# synthesizer-RF-Si4123.net
KiCad netlist of a schematic drawn in EAGLE
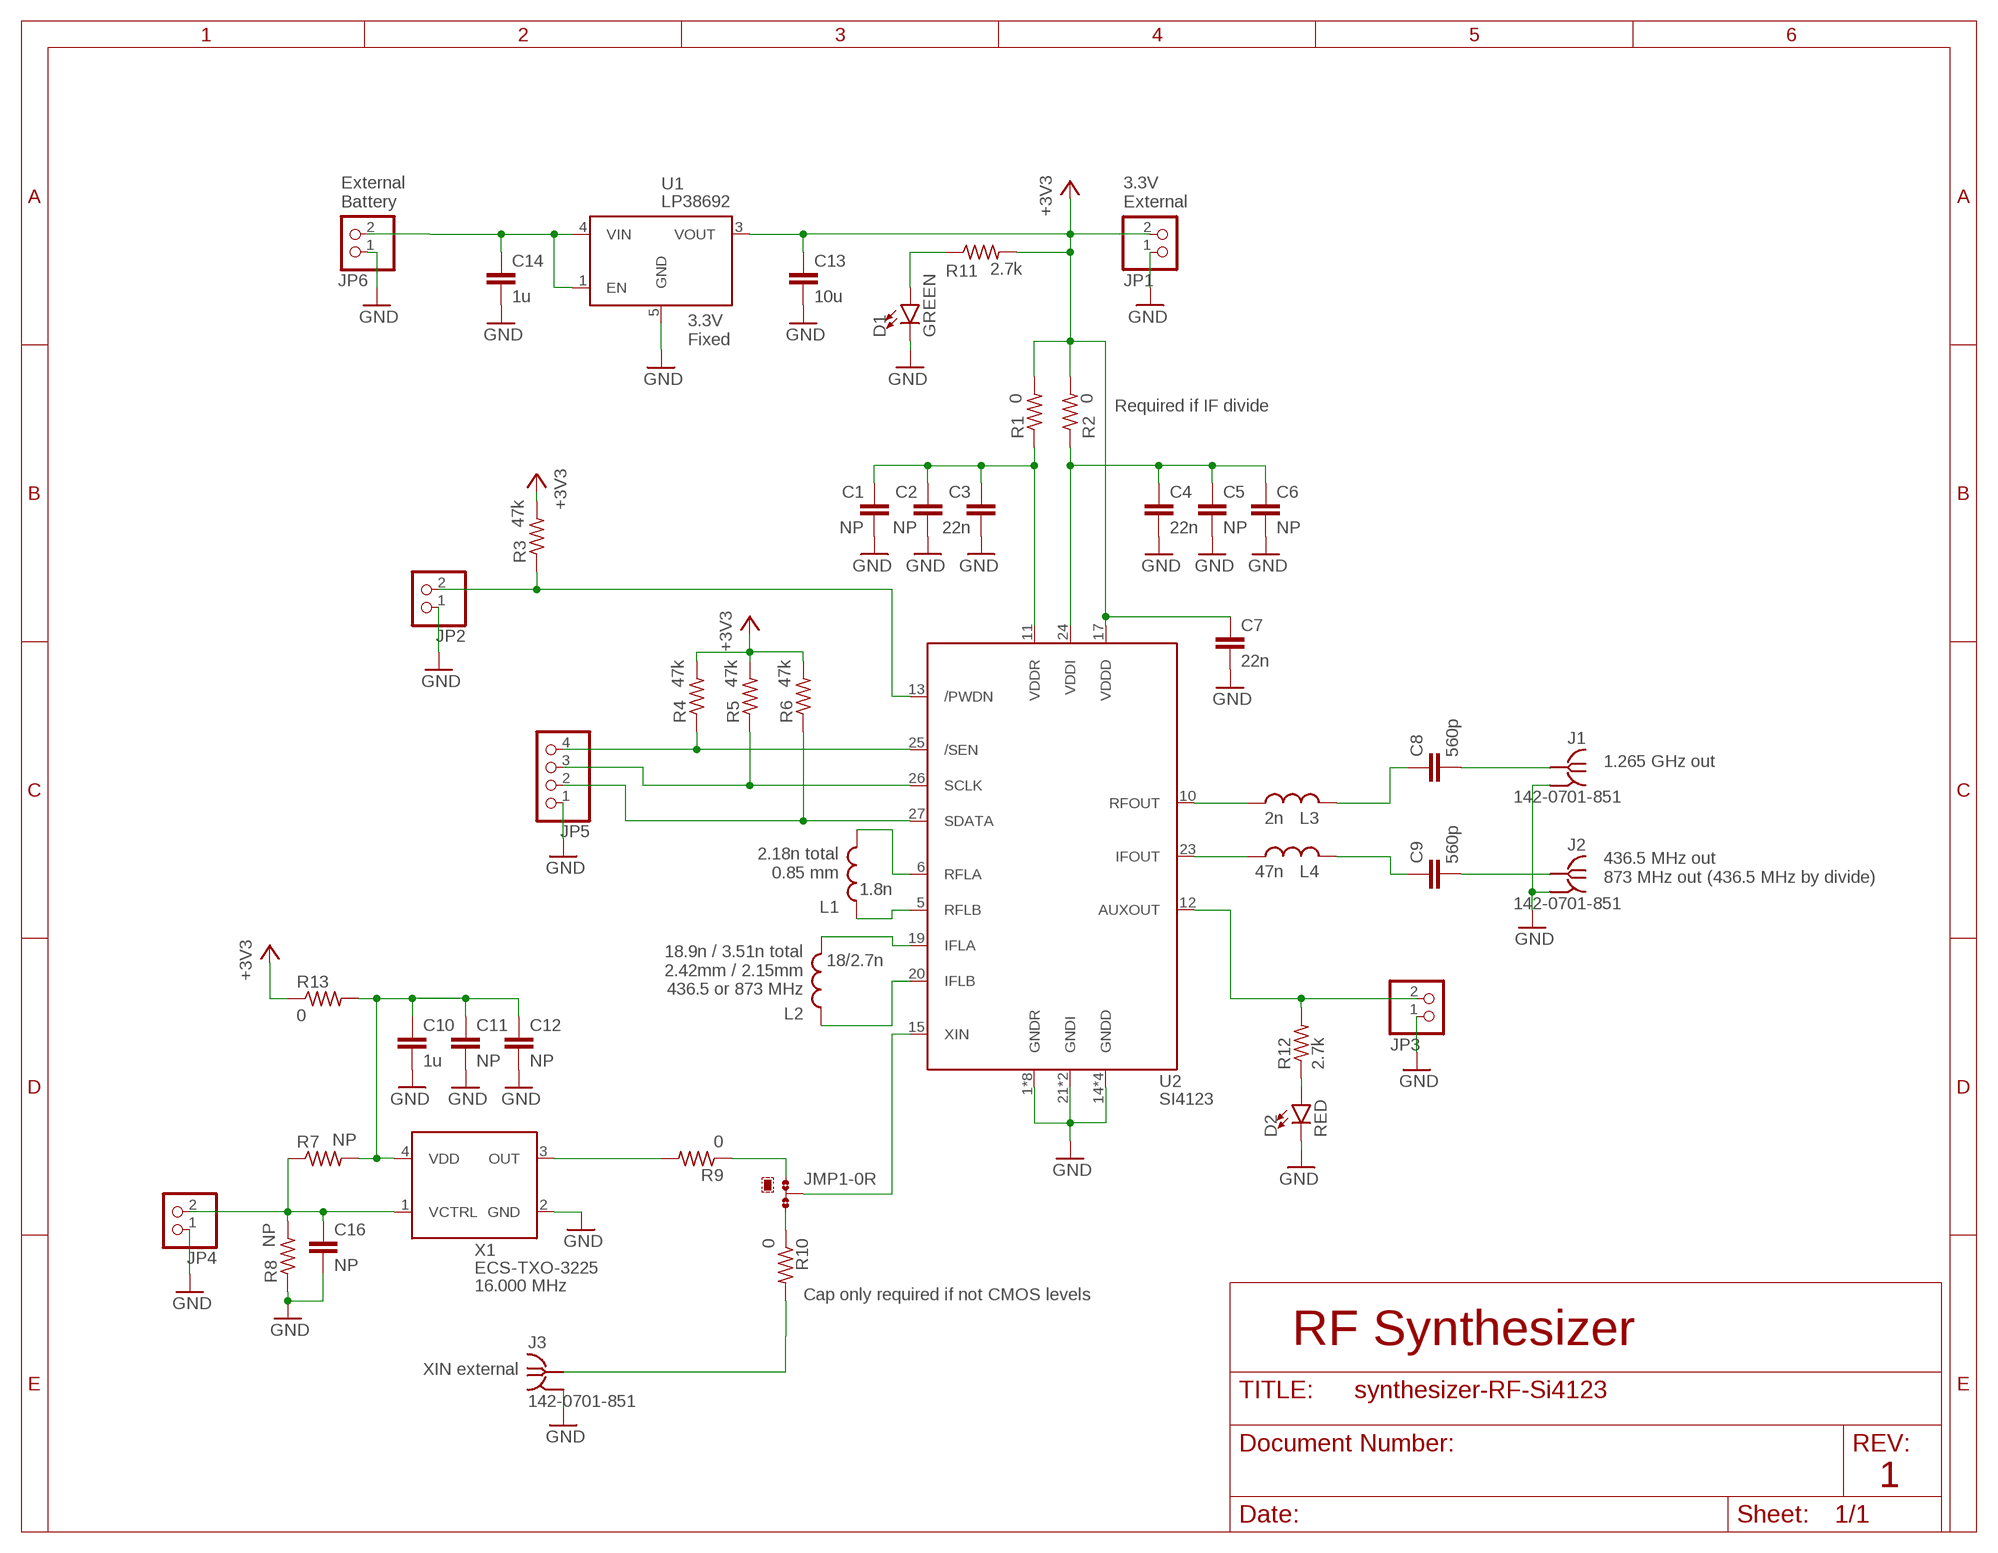
[diagram p0: schematic, sheet 1]

(export (version "E")
  (design (tool "Eeschema 10.0.6"))
  (components
    (comp (ref "C1")
      (value "NP")
      (footprint "eagle-import:.0603-B-NOSILK")
      (libsource (lib "eagle-import") (part "C-EU0603-B-NOSILK"))
    )
    (comp (ref "C2")
      (value "NP")
      (footprint "eagle-import:.0603-B-NOSILK")
      (libsource (lib "eagle-import") (part "C-EU0603-B-NOSILK"))
    )
    (comp (ref "C3")
      (value "22n")
      (footprint "eagle-import:.0603-B-NOSILK")
      (libsource (lib "eagle-import") (part "C-EU0603-B-NOSILK"))
    )
    (comp (ref "C4")
      (value "22n")
      (footprint "eagle-import:.0603-B-NOSILK")
      (libsource (lib "eagle-import") (part "C-EU0603-B-NOSILK"))
    )
    (comp (ref "C5")
      (value "NP")
      (footprint "eagle-import:.0603-B-NOSILK")
      (libsource (lib "eagle-import") (part "C-EU0603-B-NOSILK"))
    )
    (comp (ref "C6")
      (value "NP")
      (footprint "eagle-import:.0603-B-NOSILK")
      (libsource (lib "eagle-import") (part "C-EU0603-B-NOSILK"))
    )
    (comp (ref "C7")
      (value "22n")
      (footprint "eagle-import:.0603-B-NOSILK")
      (libsource (lib "eagle-import") (part "C-EU0603-B-NOSILK"))
    )
    (comp (ref "C8")
      (value "560p")
      (footprint "eagle-import:.0402-B-NOSILK")
      (libsource (lib "eagle-import") (part "C-EU0402-B-NOSILK"))
    )
    (comp (ref "C9")
      (value "560p")
      (footprint "eagle-import:.0402-B-NOSILK")
      (libsource (lib "eagle-import") (part "C-EU0402-B-NOSILK"))
    )
    (comp (ref "C10")
      (value "1u")
      (footprint "eagle-import:.0603-B-NOSILK")
      (libsource (lib "eagle-import") (part "C-EU0603-B-NOSILK"))
    )
    (comp (ref "C11")
      (value "NP")
      (footprint "eagle-import:.0603-B-NOSILK")
      (libsource (lib "eagle-import") (part "C-EU0603-B-NOSILK"))
    )
    (comp (ref "C12")
      (value "NP")
      (footprint "eagle-import:.0603-B-NOSILK")
      (libsource (lib "eagle-import") (part "C-EU0603-B-NOSILK"))
    )
    (comp (ref "C13")
      (value "10u")
      (footprint "eagle-import:.0805-B-NOSILK")
      (libsource (lib "eagle-import") (part "C-EU0805-B-NOSILK"))
    )
    (comp (ref "C14")
      (value "1u")
      (footprint "eagle-import:.0603-B-NOSILK")
      (libsource (lib "eagle-import") (part "C-EU0603-B-NOSILK"))
    )
    (comp (ref "C16")
      (value "NP")
      (footprint "eagle-import:.0603-B-NOSILK")
      (libsource (lib "eagle-import") (part "C-EU0603-B-NOSILK"))
    )
    (comp (ref "D1")
      (value "GREEN")
      (footprint "eagle-import:LED-0603")
      (libsource (lib "eagle-import") (part "LED-GREEN0603"))
    )
    (comp (ref "D2")
      (value "RED")
      (footprint "eagle-import:LED-0603")
      (libsource (lib "eagle-import") (part "LED-GREEN0603"))
    )
    (comp (ref "J1")
      (value "142-0701-851")
      (footprint "eagle-import:142-0701-851")
      (libsource (lib "eagle-import") (part "142-0701-851"))
    )
    (comp (ref "J2")
      (value "142-0701-851")
      (footprint "eagle-import:142-0701-851")
      (libsource (lib "eagle-import") (part "142-0701-851"))
    )
    (comp (ref "J3")
      (value "142-0701-851")
      (footprint "eagle-import:142-0701-851")
      (libsource (lib "eagle-import") (part "142-0701-851"))
    )
    (comp (ref "JMP1")
      (value "0R-JUMPA")
      (footprint "eagle-import:A0R-JMP")
      (libsource (lib "eagle-import") (part "0R-JUMPA"))
    )
    (comp (ref "JP1")
      (value "PINHD-1X2")
      (footprint "eagle-import:1X02")
      (libsource (lib "eagle-import") (part "PINHD-1X2"))
    )
    (comp (ref "JP2")
      (value "PINHD-1X2")
      (footprint "eagle-import:1X02")
      (libsource (lib "eagle-import") (part "PINHD-1X2"))
    )
    (comp (ref "JP3")
      (value "PINHD-1X2")
      (footprint "eagle-import:1X02")
      (libsource (lib "eagle-import") (part "PINHD-1X2"))
    )
    (comp (ref "JP4")
      (value "PINHD-1X2")
      (footprint "eagle-import:1X02")
      (libsource (lib "eagle-import") (part "PINHD-1X2"))
    )
    (comp (ref "JP5")
      (value "PINHD-1X4")
      (footprint "eagle-import:1X04")
      (libsource (lib "eagle-import") (part "PINHD-1X4"))
    )
    (comp (ref "JP6")
      (value "PINHD-1X2")
      (footprint "eagle-import:1X02")
      (libsource (lib "eagle-import") (part "PINHD-1X2"))
    )
    (comp (ref "L1")
      (value "1.8n")
      (footprint "eagle-import:.0402-C-NOSILK")
      (libsource (lib "eagle-import") (part "L-US0402-C-NOSILK"))
    )
    (comp (ref "L2")
      (value "18/2.7n")
      (footprint "eagle-import:.0402-C-NOSILK")
      (libsource (lib "eagle-import") (part "L-US0402-C-NOSILK"))
    )
    (comp (ref "L3")
      (value "2n")
      (footprint "eagle-import:.0402-B-NOSILK")
      (libsource (lib "eagle-import") (part "L-US0402-B-NOSILK"))
    )
    (comp (ref "L4")
      (value "47n")
      (footprint "eagle-import:.0402-B-NOSILK")
      (libsource (lib "eagle-import") (part "L-US0402-B-NOSILK"))
    )
    (comp (ref "R1")
      (value "0")
      (footprint "eagle-import:.0603-B-NOSILK")
      (libsource (lib "eagle-import") (part "R-US_0603-B-NOSILK"))
    )
    (comp (ref "R2")
      (value "0")
      (footprint "eagle-import:.0603-B-NOSILK")
      (libsource (lib "eagle-import") (part "R-US_0603-B-NOSILK"))
    )
    (comp (ref "R3")
      (value "47k")
      (footprint "eagle-import:.0402-B-NOSILK")
      (libsource (lib "eagle-import") (part "R-US_0402-B-NOSILK"))
    )
    (comp (ref "R4")
      (value "47k")
      (footprint "eagle-import:.0402-B-NOSILK")
      (libsource (lib "eagle-import") (part "R-US_0402-B-NOSILK"))
    )
    (comp (ref "R5")
      (value "47k")
      (footprint "eagle-import:.0402-B-NOSILK")
      (libsource (lib "eagle-import") (part "R-US_0402-B-NOSILK"))
    )
    (comp (ref "R6")
      (value "47k")
      (footprint "eagle-import:.0402-B-NOSILK")
      (libsource (lib "eagle-import") (part "R-US_0402-B-NOSILK"))
    )
    (comp (ref "R7")
      (value "NP")
      (footprint "eagle-import:.0603-B-NOSILK")
      (libsource (lib "eagle-import") (part "R-US_0603-B-NOSILK"))
    )
    (comp (ref "R8")
      (value "NP")
      (footprint "eagle-import:.0603-B-NOSILK")
      (libsource (lib "eagle-import") (part "R-US_0603-B-NOSILK"))
    )
    (comp (ref "R9")
      (value "0")
      (footprint "eagle-import:.0402-B-NOSILK")
      (libsource (lib "eagle-import") (part "R-US_0402-B-NOSILK"))
    )
    (comp (ref "R10")
      (value "0")
      (footprint "eagle-import:.0402-B-NOSILK")
      (libsource (lib "eagle-import") (part "R-US_0402-B-NOSILK"))
    )
    (comp (ref "R11")
      (value "2.7k")
      (footprint "eagle-import:.0603-B-NOSILK")
      (libsource (lib "eagle-import") (part "R-US_0603-B-NOSILK"))
    )
    (comp (ref "R12")
      (value "2.7k")
      (footprint "eagle-import:.0603-B-NOSILK")
      (libsource (lib "eagle-import") (part "R-US_0603-B-NOSILK"))
    )
    (comp (ref "R13")
      (value "0")
      (footprint "eagle-import:.0603-B-NOSILK")
      (libsource (lib "eagle-import") (part "R-US_0603-B-NOSILK"))
    )
    (comp (ref "U1")
      (value "LP38692")
      (footprint "eagle-import:SOT223-5")
      (libsource (lib "eagle-import") (part "LP38692"))
    )
    (comp (ref "U2")
      (value "SI4123")
      (footprint "eagle-import:QFN28-5X5-WITH-CENTER-PAD")
      (libsource (lib "eagle-import") (part "SI4123"))
    )
    (comp (ref "X1")
      (value "ECS-TXO-3225")
      (footprint "eagle-import:3.2X2.5")
      (libsource (lib "eagle-import") (part "ECS-TXO-3225"))
    )
  )
  (nets
    (net (code "1") (name "+3V3") (class "Default")
      (node (ref "C13") (pin "1") (pinfunction "1_1") (pintype "passive"))
      (node (ref "C7") (pin "1") (pinfunction "1_1") (pintype "passive"))
      (node (ref "JP1") (pin "2") (pinfunction "2_2") (pintype "passive"))
      (node (ref "R1") (pin "2") (pinfunction "2_2") (pintype "passive"))
      (node (ref "R11") (pin "2") (pinfunction "2_2") (pintype "passive"))
      (node (ref "R13") (pin "1") (pinfunction "1_1") (pintype "passive"))
      (node (ref "R2") (pin "2") (pinfunction "2_2") (pintype "passive"))
      (node (ref "R3") (pin "2") (pinfunction "2_2") (pintype "passive"))
      (node (ref "R4") (pin "2") (pinfunction "2_2") (pintype "passive"))
      (node (ref "R5") (pin "2") (pinfunction "2_2") (pintype "passive"))
      (node (ref "R6") (pin "2") (pinfunction "2_2") (pintype "passive"))
      (node (ref "U1") (pin "3") (pinfunction "VOUT_3") (pintype "power_in"))
      (node (ref "U2") (pin "17") (pinfunction "VDDD_17") (pintype "power_in"))
    )
    (net (code "2") (name "GND") (class "Default")
      (node (ref "C1") (pin "2") (pinfunction "2_2") (pintype "passive"))
      (node (ref "C10") (pin "2") (pinfunction "2_2") (pintype "passive"))
      (node (ref "C11") (pin "2") (pinfunction "2_2") (pintype "passive"))
      (node (ref "C12") (pin "2") (pinfunction "2_2") (pintype "passive"))
      (node (ref "C13") (pin "2") (pinfunction "2_2") (pintype "passive"))
      (node (ref "C14") (pin "2") (pinfunction "2_2") (pintype "passive"))
      (node (ref "C16") (pin "2") (pinfunction "2_2") (pintype "passive"))
      (node (ref "C2") (pin "2") (pinfunction "2_2") (pintype "passive"))
      (node (ref "C3") (pin "2") (pinfunction "2_2") (pintype "passive"))
      (node (ref "C4") (pin "2") (pinfunction "2_2") (pintype "passive"))
      (node (ref "C5") (pin "2") (pinfunction "2_2") (pintype "passive"))
      (node (ref "C6") (pin "2") (pinfunction "2_2") (pintype "passive"))
      (node (ref "C7") (pin "2") (pinfunction "2_2") (pintype "passive"))
      (node (ref "D1") (pin "C") (pinfunction "C_C") (pintype "passive"))
      (node (ref "D2") (pin "C") (pinfunction "C_C") (pintype "passive"))
      (node (ref "J1") (pin "GND1") (pinfunction "GND_GND1") (pintype "bidirectional"))
      (node (ref "J1") (pin "GND2") (pinfunction "GND_GND2") (pintype "bidirectional"))
      (node (ref "J1") (pin "GND3") (pinfunction "GND_GND3") (pintype "bidirectional"))
      (node (ref "J1") (pin "GND4") (pinfunction "GND_GND4") (pintype "bidirectional"))
      (node (ref "J2") (pin "GND1") (pinfunction "GND_GND1") (pintype "bidirectional"))
      (node (ref "J2") (pin "GND2") (pinfunction "GND_GND2") (pintype "bidirectional"))
      (node (ref "J2") (pin "GND3") (pinfunction "GND_GND3") (pintype "bidirectional"))
      (node (ref "J2") (pin "GND4") (pinfunction "GND_GND4") (pintype "bidirectional"))
      (node (ref "J3") (pin "GND1") (pinfunction "GND_GND1") (pintype "bidirectional"))
      (node (ref "J3") (pin "GND2") (pinfunction "GND_GND2") (pintype "bidirectional"))
      (node (ref "J3") (pin "GND3") (pinfunction "GND_GND3") (pintype "bidirectional"))
      (node (ref "J3") (pin "GND4") (pinfunction "GND_GND4") (pintype "bidirectional"))
      (node (ref "JP1") (pin "1") (pinfunction "1_1") (pintype "passive"))
      (node (ref "JP2") (pin "1") (pinfunction "1_1") (pintype "passive"))
      (node (ref "JP3") (pin "1") (pinfunction "1_1") (pintype "passive"))
      (node (ref "JP4") (pin "1") (pinfunction "1_1") (pintype "passive"))
      (node (ref "JP5") (pin "1") (pinfunction "1_1") (pintype "passive"))
      (node (ref "JP6") (pin "1") (pinfunction "1_1") (pintype "passive"))
      (node (ref "R8") (pin "1") (pinfunction "1_1") (pintype "passive"))
      (node (ref "U1") (pin "5") (pinfunction "GND_5") (pintype "power_in"))
      (node (ref "U2") (pin "1") (pinfunction "GNDR_1") (pintype "power_in"))
      (node (ref "U2") (pin "14") (pinfunction "GNDD_14") (pintype "power_in"))
      (node (ref "U2") (pin "16") (pinfunction "GNDD_16") (pintype "power_in"))
      (node (ref "U2") (pin "18") (pinfunction "GNDD_18") (pintype "power_in"))
      (node (ref "U2") (pin "2") (pinfunction "GNDR_2") (pintype "power_in"))
      (node (ref "U2") (pin "21") (pinfunction "GNDI_21") (pintype "power_in"))
      (node (ref "U2") (pin "22") (pinfunction "GNDI_22") (pintype "power_in"))
      (node (ref "U2") (pin "28") (pinfunction "GNDR_28") (pintype "power_in"))
      (node (ref "U2") (pin "3") (pinfunction "GNDR_3") (pintype "power_in"))
      (node (ref "U2") (pin "4") (pinfunction "GNDR_4") (pintype "power_in"))
      (node (ref "U2") (pin "7") (pinfunction "GNDR_7") (pintype "power_in"))
      (node (ref "U2") (pin "8") (pinfunction "GNDR_8") (pintype "power_in"))
      (node (ref "U2") (pin "9") (pinfunction "GNDR_9") (pintype "power_in"))
      (node (ref "U2") (pin "PAD") (pinfunction "GNDD_PAD") (pintype "power_in"))
      (node (ref "X1") (pin "2") (pinfunction "GND_2") (pintype "power_in"))
    )
    (net (code "3") (name "Net-(C8-Pad1)") (class "Default")
      (node (ref "C8") (pin "1") (pinfunction "1_1") (pintype "passive"))
      (node (ref "L3") (pin "2") (pinfunction "2_2") (pintype "passive"))
    )
    (net (code "4") (name "Net-(C9-Pad1)") (class "Default")
      (node (ref "C9") (pin "1") (pinfunction "1_1") (pintype "passive"))
      (node (ref "L4") (pin "2") (pinfunction "2_2") (pintype "passive"))
    )
    (net (code "5") (name "Net-(D1-PadA)") (class "Default")
      (node (ref "D1") (pin "A") (pinfunction "A_A") (pintype "passive"))
      (node (ref "R11") (pin "1") (pinfunction "1_1") (pintype "passive"))
    )
    (net (code "6") (name "Net-(D2-PadA)") (class "Default")
      (node (ref "D2") (pin "A") (pinfunction "A_A") (pintype "passive"))
      (node (ref "R12") (pin "1") (pinfunction "1_1") (pintype "passive"))
    )
    (net (code "7") (name "Net-(J1-RF)") (class "Default")
      (node (ref "C8") (pin "2") (pinfunction "2_2") (pintype "passive"))
      (node (ref "J1") (pin "RF1") (pinfunction "RF_RF1") (pintype "bidirectional"))
    )
    (net (code "8") (name "Net-(J2-RF)") (class "Default")
      (node (ref "C9") (pin "2") (pinfunction "2_2") (pintype "passive"))
      (node (ref "J2") (pin "RF1") (pinfunction "RF_RF1") (pintype "bidirectional"))
    )
    (net (code "9") (name "Net-(J3-RF)") (class "Default")
      (node (ref "J3") (pin "RF1") (pinfunction "RF_RF1") (pintype "bidirectional"))
      (node (ref "R10") (pin "2") (pinfunction "2_2") (pintype "passive"))
    )
    (net (code "10") (name "Net-(JMP1-Pad1)") (class "Default")
      (node (ref "JMP1") (pin "1") (pinfunction "1_1") (pintype "passive"))
      (node (ref "R9") (pin "1") (pinfunction "1_1") (pintype "passive"))
    )
    (net (code "11") (name "Net-(JMP1-Pad3)") (class "Default")
      (node (ref "JMP1") (pin "3") (pinfunction "3_3") (pintype "passive"))
      (node (ref "R10") (pin "1") (pinfunction "1_1") (pintype "passive"))
    )
    (net (code "12") (name "Net-(U1-EN)") (class "Default")
      (node (ref "C14") (pin "1") (pinfunction "1_1") (pintype "passive"))
      (node (ref "JP6") (pin "2") (pinfunction "2_2") (pintype "passive"))
      (node (ref "U1") (pin "1") (pinfunction "EN_1") (pintype "input"))
      (node (ref "U1") (pin "4") (pinfunction "VIN_4") (pintype "power_in"))
    )
    (net (code "13") (name "Net-(U2-AUXOUT)") (class "Default")
      (node (ref "JP3") (pin "2") (pinfunction "2_2") (pintype "passive"))
      (node (ref "R12") (pin "2") (pinfunction "2_2") (pintype "passive"))
      (node (ref "U2") (pin "12") (pinfunction "AUXOUT_12") (pintype "output"))
    )
    (net (code "14") (name "Net-(U2-IFLA)") (class "Default")
      (node (ref "L2") (pin "2") (pinfunction "2_2") (pintype "passive"))
      (node (ref "U2") (pin "19") (pinfunction "IFLA_19") (pintype "input"))
    )
    (net (code "15") (name "Net-(U2-IFLB)") (class "Default")
      (node (ref "L2") (pin "1") (pinfunction "1_1") (pintype "passive"))
      (node (ref "U2") (pin "20") (pinfunction "IFLB_20") (pintype "input"))
    )
    (net (code "16") (name "Net-(U2-IFOUT)") (class "Default")
      (node (ref "L4") (pin "1") (pinfunction "1_1") (pintype "passive"))
      (node (ref "U2") (pin "23") (pinfunction "IFOUT_23") (pintype "output"))
    )
    (net (code "17") (name "Net-(U2-RFLA)") (class "Default")
      (node (ref "L1") (pin "2") (pinfunction "2_2") (pintype "passive"))
      (node (ref "U2") (pin "6") (pinfunction "RFLA_6") (pintype "input"))
    )
    (net (code "18") (name "Net-(U2-RFLB)") (class "Default")
      (node (ref "L1") (pin "1") (pinfunction "1_1") (pintype "passive"))
      (node (ref "U2") (pin "5") (pinfunction "RFLB_5") (pintype "input"))
    )
    (net (code "19") (name "Net-(U2-RFOUT)") (class "Default")
      (node (ref "L3") (pin "1") (pinfunction "1_1") (pintype "passive"))
      (node (ref "U2") (pin "10") (pinfunction "RFOUT_10") (pintype "output"))
    )
    (net (code "20") (name "Net-(U2-SCLK)") (class "Default")
      (node (ref "JP5") (pin "3") (pinfunction "3_3") (pintype "passive"))
      (node (ref "R5") (pin "1") (pinfunction "1_1") (pintype "passive"))
      (node (ref "U2") (pin "26") (pinfunction "SCLK_26") (pintype "input"))
    )
    (net (code "21") (name "Net-(U2-SDATA)") (class "Default")
      (node (ref "JP5") (pin "2") (pinfunction "2_2") (pintype "passive"))
      (node (ref "R6") (pin "1") (pinfunction "1_1") (pintype "passive"))
      (node (ref "U2") (pin "27") (pinfunction "SDATA_27") (pintype "input"))
    )
    (net (code "22") (name "Net-(U2-VDDI)") (class "Default")
      (node (ref "C4") (pin "1") (pinfunction "1_1") (pintype "passive"))
      (node (ref "C5") (pin "1") (pinfunction "1_1") (pintype "passive"))
      (node (ref "C6") (pin "1") (pinfunction "1_1") (pintype "passive"))
      (node (ref "R2") (pin "1") (pinfunction "1_1") (pintype "passive"))
      (node (ref "U2") (pin "24") (pinfunction "VDDI_24") (pintype "power_in"))
    )
    (net (code "23") (name "Net-(U2-VDDR)") (class "Default")
      (node (ref "C1") (pin "1") (pinfunction "1_1") (pintype "passive"))
      (node (ref "C2") (pin "1") (pinfunction "1_1") (pintype "passive"))
      (node (ref "C3") (pin "1") (pinfunction "1_1") (pintype "passive"))
      (node (ref "R1") (pin "1") (pinfunction "1_1") (pintype "passive"))
      (node (ref "U2") (pin "11") (pinfunction "VDDR_11") (pintype "power_in"))
    )
    (net (code "24") (name "Net-(U2-XIN)") (class "Default")
      (node (ref "JMP1") (pin "2") (pinfunction "2_2") (pintype "passive"))
      (node (ref "U2") (pin "15") (pinfunction "XIN_15") (pintype "input"))
    )
    (net (code "25") (name "Net-(U2-{slash}PWDN)") (class "Default")
      (node (ref "JP2") (pin "2") (pinfunction "2_2") (pintype "passive"))
      (node (ref "R3") (pin "1") (pinfunction "1_1") (pintype "passive"))
      (node (ref "U2") (pin "13") (pinfunction "/PWDN_13") (pintype "input"))
    )
    (net (code "26") (name "Net-(U2-{slash}SEN)") (class "Default")
      (node (ref "JP5") (pin "4") (pinfunction "4_4") (pintype "passive"))
      (node (ref "R4") (pin "1") (pinfunction "1_1") (pintype "passive"))
      (node (ref "U2") (pin "25") (pinfunction "/SEN_25") (pintype "input"))
    )
    (net (code "27") (name "Net-(X1-OUT)") (class "Default")
      (node (ref "R9") (pin "2") (pinfunction "2_2") (pintype "passive"))
      (node (ref "X1") (pin "3") (pinfunction "OUT_3") (pintype "output"))
    )
    (net (code "28") (name "Net-(X1-VCTRL)") (class "Default")
      (node (ref "C16") (pin "1") (pinfunction "1_1") (pintype "passive"))
      (node (ref "JP4") (pin "2") (pinfunction "2_2") (pintype "passive"))
      (node (ref "R7") (pin "1") (pinfunction "1_1") (pintype "passive"))
      (node (ref "R8") (pin "2") (pinfunction "2_2") (pintype "passive"))
      (node (ref "X1") (pin "1") (pinfunction "VCTRL_1") (pintype "input"))
    )
    (net (code "29") (name "Net-(X1-VDD)") (class "Default")
      (node (ref "C10") (pin "1") (pinfunction "1_1") (pintype "passive"))
      (node (ref "C11") (pin "1") (pinfunction "1_1") (pintype "passive"))
      (node (ref "C12") (pin "1") (pinfunction "1_1") (pintype "passive"))
      (node (ref "R13") (pin "2") (pinfunction "2_2") (pintype "passive"))
      (node (ref "R7") (pin "2") (pinfunction "2_2") (pintype "passive"))
      (node (ref "X1") (pin "4") (pinfunction "VDD_4") (pintype "power_in"))
    )
  )
)
